# SCH_nfc-card_2024-03-30.net
KiCad netlist of a schematic drawn in EasyEDA
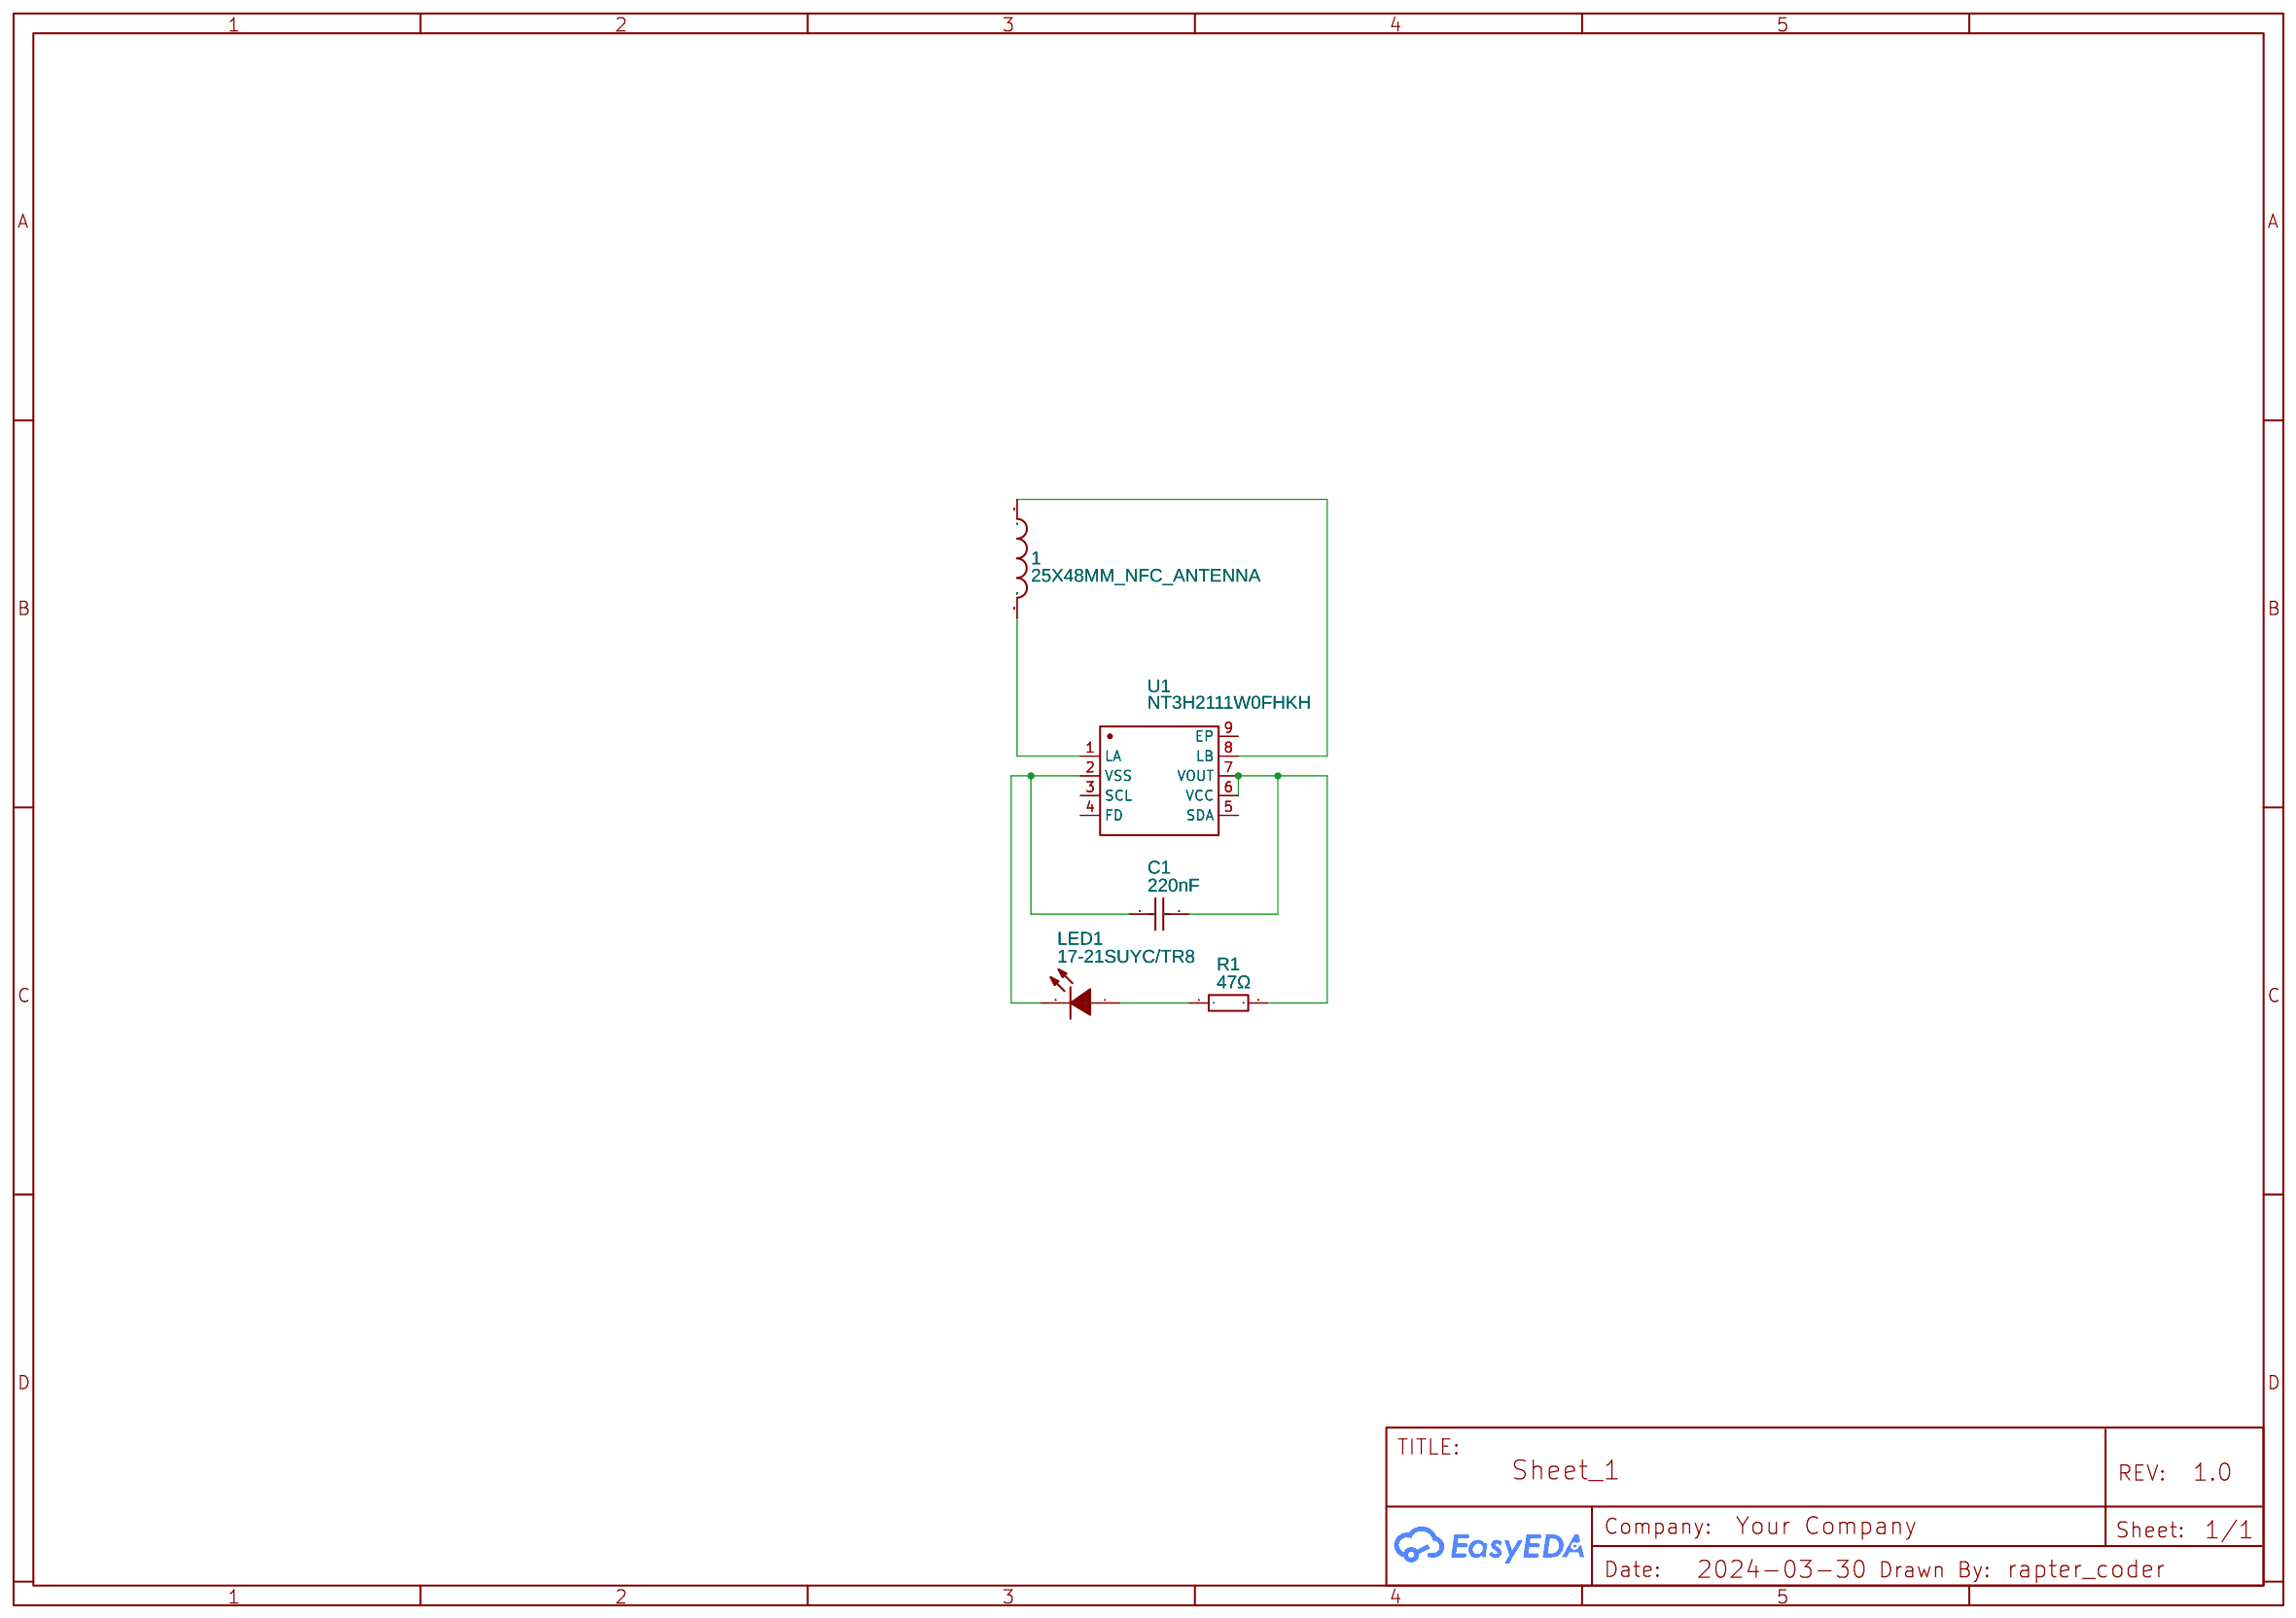
[diagram p0: schematic sheet]

(export (version "E")
  (design (tool "Eeschema 10.0.6"))
  (components
    (comp (ref "1") (value "25X48MM_NFC_ANTENNA") (libsource (lib "") (part "25X48MM_NFC_ANTENNA")))
    (comp (ref "C1")
      (value "220nF")
      (fields
        (field (name "Manufacturer Part") "CL10B224KA8NNNC")
        (field (name "Manufacturer") "SAMSUNG(三星)")
      )
      (libsource (lib "") (part "CL10B224KA8NNNC"))
    )
    (comp (ref "LED1")
      (value "17-21SUYC/TR8")
      (fields (field (name "Manufacturer Part") "KT-0805黄灯") (field (name "Manufacturer") "KENTO"))
      (libsource (lib "") (part "17-21SUYC/TR8"))
    )
    (comp (ref "R1")
      (value "47Ω")
      (fields
        (field (name "Manufacturer Part") "0603WAF470JT5E")
        (field (name "Manufacturer") "UNI-ROYAL(厚声)")
      )
      (libsource (lib "") (part "0603WAF470JT5E"))
    )
    (comp (ref "U1")
      (value "NT3H2111W0FHKH")
      (fields (field (name "Manufacturer") "NXP(恩智浦)"))
      (libsource (lib "") (part "NT3H2111W0FHKH"))
    )
  )
  (nets
    (net (code "1") (name "Net-(LED1-+)") (class "Default")
      (node (ref "LED1") (pin "1") (pinfunction "+_1") (pintype "unspecified"))
      (node (ref "R1") (pin "1") (pinfunction "1_1") (pintype "input"))
    )
    (net (code "2") (name "Net-(LED1--)") (class "Default")
      (node (ref "C1") (pin "1") (pinfunction "1_1") (pintype "input"))
      (node (ref "LED1") (pin "2") (pinfunction "-_2") (pintype "unspecified"))
      (node (ref "U1") (pin "2") (pinfunction "VSS_2") (pintype "unspecified"))
    )
    (net (code "3") (name "Net-(U1-LA)") (class "Default")
      (node (ref "1") (pin "P$2") (pinfunction "P$2_P$2") (pintype "bidirectional"))
      (node (ref "U1") (pin "1") (pinfunction "LA_1") (pintype "unspecified"))
    )
    (net (code "4") (name "Net-(U1-LB)") (class "Default")
      (node (ref "1") (pin "P$1") (pinfunction "P$1_P$1") (pintype "bidirectional"))
      (node (ref "U1") (pin "8") (pinfunction "LB_8") (pintype "unspecified"))
    )
    (net (code "5") (name "Net-(U1-VCC)") (class "Default")
      (node (ref "C1") (pin "2") (pinfunction "2_2") (pintype "input"))
      (node (ref "R1") (pin "2") (pinfunction "2_2") (pintype "input"))
      (node (ref "U1") (pin "6") (pinfunction "VCC_6") (pintype "unspecified"))
      (node (ref "U1") (pin "7") (pinfunction "VOUT_7") (pintype "unspecified"))
    )
    (net (code "6") (name "unconnected-(U1-EP-Pad9)") (class "Default")
      (node (ref "U1") (pin "9") (pinfunction "EP_9") (pintype "unspecified"))
    )
    (net (code "7") (name "unconnected-(U1-FD-Pad4)") (class "Default")
      (node (ref "U1") (pin "4") (pinfunction "FD_4") (pintype "unspecified"))
    )
    (net (code "8") (name "unconnected-(U1-SCL-Pad3)") (class "Default")
      (node (ref "U1") (pin "3") (pinfunction "SCL_3") (pintype "unspecified"))
    )
    (net (code "9") (name "unconnected-(U1-SDA-Pad5)") (class "Default")
      (node (ref "U1") (pin "5") (pinfunction "SDA_5") (pintype "unspecified"))
    )
  )
)
